# Top.net
KiCad netlist of a schematic drawn in Altium Designer
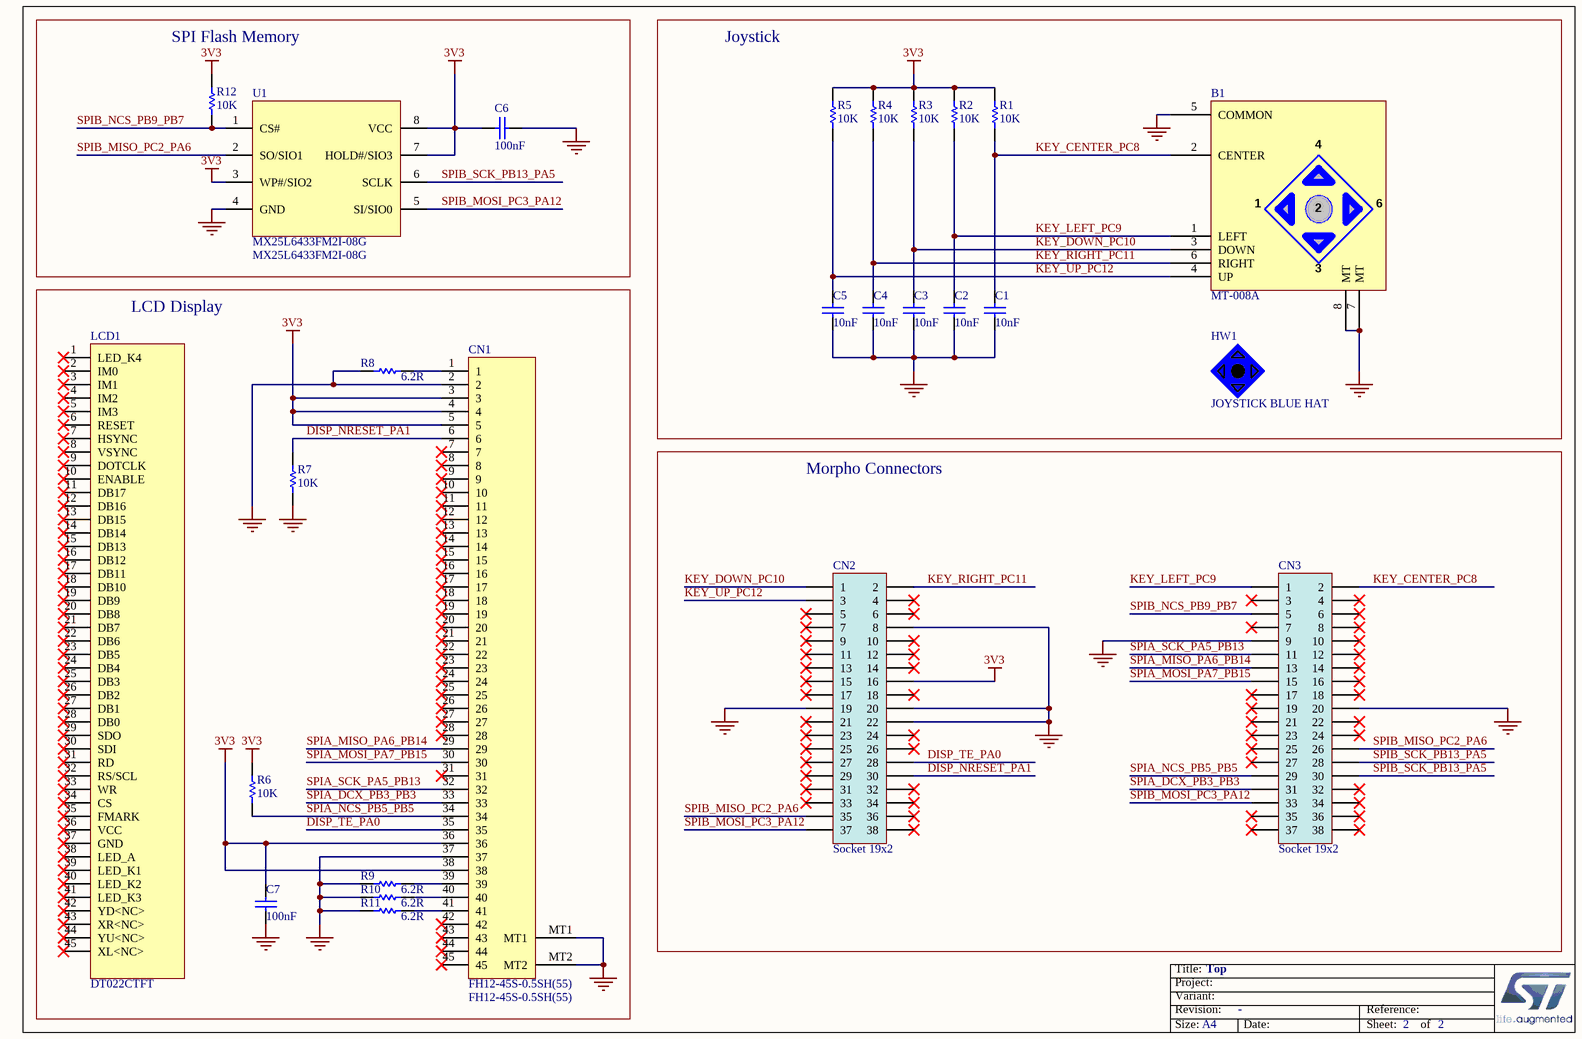
[diagram p0: Top.SchDoc]

(export (version "E")
  (design (tool "Eeschema 10.0.6"))
  (components
    (comp (ref "B1")
      (value "MT-008A")
      (footprint "SWI_XIEJIA_MT-008A_6P")
      (description "Joystick, 4 dir, 1 OK")
      (fields
        (field (name "INTERNAL_PART_NUMBER") "MCD-00132")
        (field (name "MANUFACTURER") "XIEJIA ELECTRONICS")
        (field (name "PROVIDED_BY") "SUBCO")
      )
      (libsource (lib "MCD_PARTS_database") (part "Joystick MT-008A_M"))
    )
    (comp (ref "C1")
      (value "10nF")
      (footprint "C0603")
      (description "Capacitor,10nF,100V,X7R,10%,0603")
      (fields
        (field (name "INTERNAL_PART_NUMBER") "MCD-01098")
        (field (name "MANUFACTURER_PART_NUMBER") "CC0603KRX7R0BB103")
        (field (name "PROVIDED_BY") "SUBCO")
      )
      (libsource (lib "MCD_PARTS_database") (part "Capacitor"))
    )
    (comp (ref "C2")
      (value "10nF")
      (footprint "C0603")
      (description "Capacitor,10nF,100V,X7R,10%,0603")
      (fields
        (field (name "INTERNAL_PART_NUMBER") "MCD-01098")
        (field (name "MANUFACTURER_PART_NUMBER") "CC0603KRX7R0BB103")
        (field (name "PROVIDED_BY") "SUBCO")
      )
      (libsource (lib "MCD_PARTS_database") (part "Capacitor"))
    )
    (comp (ref "C3")
      (value "10nF")
      (footprint "C0603")
      (description "Capacitor,10nF,100V,X7R,10%,0603")
      (fields
        (field (name "INTERNAL_PART_NUMBER") "MCD-01098")
        (field (name "MANUFACTURER_PART_NUMBER") "CC0603KRX7R0BB103")
        (field (name "PROVIDED_BY") "SUBCO")
      )
      (libsource (lib "MCD_PARTS_database") (part "Capacitor"))
    )
    (comp (ref "C4")
      (value "10nF")
      (footprint "C0603")
      (description "Capacitor,10nF,100V,X7R,10%,0603")
      (fields
        (field (name "INTERNAL_PART_NUMBER") "MCD-01098")
        (field (name "MANUFACTURER_PART_NUMBER") "CC0603KRX7R0BB103")
        (field (name "PROVIDED_BY") "SUBCO")
      )
      (libsource (lib "MCD_PARTS_database") (part "Capacitor"))
    )
    (comp (ref "C5")
      (value "10nF")
      (footprint "C0603")
      (description "Capacitor,10nF,100V,X7R,10%,0603")
      (fields
        (field (name "INTERNAL_PART_NUMBER") "MCD-01098")
        (field (name "MANUFACTURER_PART_NUMBER") "CC0603KRX7R0BB103")
        (field (name "PROVIDED_BY") "SUBCO")
      )
      (libsource (lib "MCD_PARTS_database") (part "Capacitor"))
    )
    (comp (ref "C6")
      (value "100nF")
      (footprint "C0603")
      (description "Capacitor, MLCC, 100nF, 6V3, X5R, 10%, 0603, T=0,8mm")
      (fields
        (field (name "INTERNAL_PART_NUMBER") "MCD-00237")
        (field (name "MANUFACTURER_PART_NUMBER") "CC0603KRX5R5BB104")
        (field (name "PROVIDED_BY") "SUBCO")
      )
      (libsource (lib "MCD_PARTS_database") (part "Capacitor"))
    )
    (comp (ref "C7")
      (value "100nF")
      (footprint "C0603")
      (description "Capacitor, MLCC, 100nF, 6V3, X5R, 10%, 0603, T=0,8mm")
      (fields
        (field (name "INTERNAL_PART_NUMBER") "MCD-00237")
        (field (name "MANUFACTURER_PART_NUMBER") "CC0603KRX5R5BB104")
        (field (name "PROVIDED_BY") "SUBCO")
      )
      (libsource (lib "MCD_PARTS_database") (part "Capacitor"))
    )
    (comp (ref "CN1")
      (value "FH12-45S-0.5SH(55)")
      (footprint "CON_HRS_FH12-45S-05SH")
      (description "45 pins P 0.5 surface mount connector")
      (fields
        (field (name "INTERNAL_PART_NUMBER") "MCD-01980")
        (field (name "ALTIUM_VALUE") "FH12-45S-0.5SH(55)")
        (field (name "MANUFACTURER") "HIROSE")
        (field (name "PROVIDED_BY") "SUBCO")
      )
      (libsource (lib "MCD_PARTS_database") (part "FH12-45S-0.5SH(55)"))
    )
    (comp (ref "CN2")
      (value "Socket 19x2")
      (footprint "CON_SAMTEC_SSW-119-01-X-D")
      (description "Socket, 19x2, 2.54mm, VR, TH, Height 8.51mm/2.64mm")
      (fields
        (field (name "INTERNAL_PART_NUMBER") "MCD-01845")
        (field (name "MANUFACTURER_PART_NUMBER") "SSW-119-01-x-D")
        (field (name "PROVIDED_BY") "SUBCO")
      )
      (libsource (lib "MCD_PARTS_database") (part "Socket 19x2"))
    )
    (comp (ref "CN3")
      (value "Socket 19x2")
      (footprint "CON_SAMTEC_SSW-119-01-X-D")
      (description "Socket, 19x2, 2.54mm, VR, TH, Height 8.51mm/2.64mm")
      (fields
        (field (name "INTERNAL_PART_NUMBER") "MCD-01845")
        (field (name "MANUFACTURER_PART_NUMBER") "SSW-119-01-x-D")
        (field (name "PROVIDED_BY") "SUBCO")
      )
      (libsource (lib "MCD_PARTS_database") (part "Socket 19x2"))
    )
    (comp (ref "HW1")
      (value "JOYSTICK BLUE HAT")
      (description "Joystick Blue Hat")
      (fields
        (field (name "INTERNAL_PART_NUMBER") "MCD-01337")
        (field (name "MANUFACTURER_PART_NUMBER") "PB-504")
        (field (name "PROVIDED_BY") "SUBCO")
      )
      (libsource (lib "MCD_PARTS_database") (part "JOYSTICK_BLUE_HAT"))
    )
    (comp (ref "LCD1")
      (value "DT022CTFT")
      (footprint "LCD_DISPLAYTECH_DT022CTFT_45P_P050")
      (description "240x320 2.2inch display")
      (fields
        (field (name "INTERNAL_PART_NUMBER") "MCD-01982")
        (field (name "MANUFACTURER") "DISPLAYTECH")
        (field (name "PROVIDED_BY") "SUBCO")
      )
      (libsource (lib "MCD_PARTS_database") (part "DT022CTFT"))
    )
    (comp (ref "R1")
      (value "10K")
      (footprint "R0603")
      (description "Resistor,10K,0603,1%,1/10W")
      (fields
        (field (name "INTERNAL_PART_NUMBER") "MCD-00220")
        (field (name "MANUFACTURER_PART_NUMBER") "RC0603FR-0710KL")
        (field (name "PROVIDED_BY") "SUBCO")
      )
      (libsource (lib "MCD_PARTS_database") (part "Resistor"))
    )
    (comp (ref "R2")
      (value "10K")
      (footprint "R0603")
      (description "Resistor,10K,0603,1%,1/10W")
      (fields
        (field (name "INTERNAL_PART_NUMBER") "MCD-00220")
        (field (name "MANUFACTURER_PART_NUMBER") "RC0603FR-0710KL")
        (field (name "PROVIDED_BY") "SUBCO")
      )
      (libsource (lib "MCD_PARTS_database") (part "Resistor"))
    )
    (comp (ref "R3")
      (value "10K")
      (footprint "R0603")
      (description "Resistor,10K,0603,1%,1/10W")
      (fields
        (field (name "INTERNAL_PART_NUMBER") "MCD-00220")
        (field (name "MANUFACTURER_PART_NUMBER") "RC0603FR-0710KL")
        (field (name "PROVIDED_BY") "SUBCO")
      )
      (libsource (lib "MCD_PARTS_database") (part "Resistor"))
    )
    (comp (ref "R4")
      (value "10K")
      (footprint "R0603")
      (description "Resistor,10K,0603,1%,1/10W")
      (fields
        (field (name "INTERNAL_PART_NUMBER") "MCD-00220")
        (field (name "MANUFACTURER_PART_NUMBER") "RC0603FR-0710KL")
        (field (name "PROVIDED_BY") "SUBCO")
      )
      (libsource (lib "MCD_PARTS_database") (part "Resistor"))
    )
    (comp (ref "R5")
      (value "10K")
      (footprint "R0603")
      (description "Resistor,10K,0603,1%,1/10W")
      (fields
        (field (name "INTERNAL_PART_NUMBER") "MCD-00220")
        (field (name "MANUFACTURER_PART_NUMBER") "RC0603FR-0710KL")
        (field (name "PROVIDED_BY") "SUBCO")
      )
      (libsource (lib "MCD_PARTS_database") (part "Resistor"))
    )
    (comp (ref "R6")
      (value "10K")
      (footprint "R0603")
      (description "Resistor,10K,0603,1%,1/10W")
      (fields
        (field (name "INTERNAL_PART_NUMBER") "MCD-00220")
        (field (name "MANUFACTURER_PART_NUMBER") "RC0603FR-0710KL")
        (field (name "PROVIDED_BY") "SUBCO")
      )
      (libsource (lib "MCD_PARTS_database") (part "Resistor"))
    )
    (comp (ref "R7")
      (value "10K")
      (footprint "R0603")
      (description "Resistor,10K,0603,1%,1/10W")
      (fields
        (field (name "INTERNAL_PART_NUMBER") "MCD-00220")
        (field (name "MANUFACTURER_PART_NUMBER") "RC0603FR-0710KL")
        (field (name "PROVIDED_BY") "SUBCO")
      )
      (libsource (lib "MCD_PARTS_database") (part "Resistor"))
    )
    (comp (ref "R8")
      (value "6.2R")
      (footprint "R1206_H0P55")
      (description "Resistor,6.2R,1206,1%,0.5W")
      (fields
        (field (name "INTERNAL_PART_NUMBER") "MCD-02101")
        (field (name "MANUFACTURER_PART_NUMBER") "ERJ8BQF6R2V")
        (field (name "PROVIDED_BY") "SUBCO")
      )
      (libsource (lib "MCD_PARTS_database") (part "Resistor"))
    )
    (comp (ref "R9")
      (value "6.2R")
      (footprint "R1206_H0P55")
      (description "Resistor,6.2R,1206,1%,0.5W")
      (fields
        (field (name "INTERNAL_PART_NUMBER") "MCD-02101")
        (field (name "MANUFACTURER_PART_NUMBER") "ERJ8BQF6R2V")
        (field (name "PROVIDED_BY") "SUBCO")
      )
      (libsource (lib "MCD_PARTS_database") (part "Resistor"))
    )
    (comp (ref "R10")
      (value "6.2R")
      (footprint "R1206_H0P55")
      (description "Resistor,6.2R,1206,1%,0.5W")
      (fields
        (field (name "INTERNAL_PART_NUMBER") "MCD-02101")
        (field (name "MANUFACTURER_PART_NUMBER") "ERJ8BQF6R2V")
        (field (name "PROVIDED_BY") "SUBCO")
      )
      (libsource (lib "MCD_PARTS_database") (part "Resistor"))
    )
    (comp (ref "R11")
      (value "6.2R")
      (footprint "R1206_H0P55")
      (description "Resistor,6.2R,1206,1%,0.5W")
      (fields
        (field (name "INTERNAL_PART_NUMBER") "MCD-02101")
        (field (name "MANUFACTURER_PART_NUMBER") "ERJ8BQF6R2V")
        (field (name "PROVIDED_BY") "SUBCO")
      )
      (libsource (lib "MCD_PARTS_database") (part "Resistor"))
    )
    (comp (ref "R12")
      (value "10K")
      (footprint "R0603")
      (description "Resistor,10K,0603,1%,1/10W")
      (fields
        (field (name "INTERNAL_PART_NUMBER") "MCD-00220")
        (field (name "MANUFACTURER_PART_NUMBER") "RC0603FR-0710KL")
        (field (name "PROVIDED_BY") "SUBCO")
      )
      (libsource (lib "MCD_PARTS_database") (part "Resistor"))
    )
    (comp (ref "U1")
      (value "MX25L6433FM2I-08G")
      (footprint "ICC_SOP8_5P23X5P28_P127")
      (fields
        (field (name "INTERNAL_PART_NUMBER") "MCD-01981")
        (field (name "ALTIUM_VALUE") "MX25L6433FM2I-08G")
        (field (name "MANUFACTURER") "MACRONIX")
        (field (name "PROVIDED_BY") "SUBCO")
      )
      (libsource (lib "MCD_PARTS_database") (part "MX25L6433FM2I-08G"))
    )
  )
  (nets
    (net (code "1") (name "/DISP_NRESET_PA1") (class "Default")
      (node (ref "CN1") (pin "6") (pinfunction "6_6") (pintype "passive"))
      (node (ref "CN2") (pin "30") (pinfunction "30_30") (pintype "passive"))
      (node (ref "R7") (pin "2") (pinfunction "2_2") (pintype "passive"))
    )
    (net (code "2") (name "/DISP_TE_PA0") (class "Default")
      (node (ref "CN1") (pin "35") (pinfunction "35_35") (pintype "passive"))
      (node (ref "CN2") (pin "28") (pinfunction "28_28") (pintype "passive"))
    )
    (net (code "3") (name "/KEY_CENTER_PC8") (class "Default")
      (node (ref "B1") (pin "2") (pinfunction "CENTER_2") (pintype "passive"))
      (node (ref "C1") (pin "2") (pinfunction "2_2") (pintype "passive"))
      (node (ref "CN3") (pin "2") (pinfunction "2_2") (pintype "passive"))
      (node (ref "R1") (pin "2") (pinfunction "2_2") (pintype "passive"))
    )
    (net (code "4") (name "/KEY_DOWN_PC10") (class "Default")
      (node (ref "B1") (pin "3") (pinfunction "DOWN_3") (pintype "passive"))
      (node (ref "C3") (pin "2") (pinfunction "2_2") (pintype "passive"))
      (node (ref "CN2") (pin "1") (pinfunction "1_1") (pintype "passive"))
      (node (ref "R3") (pin "1") (pinfunction "1_1") (pintype "passive"))
    )
    (net (code "5") (name "/KEY_LEFT_PC9") (class "Default")
      (node (ref "B1") (pin "1") (pinfunction "LEFT_1") (pintype "passive"))
      (node (ref "C2") (pin "2") (pinfunction "2_2") (pintype "passive"))
      (node (ref "CN3") (pin "1") (pinfunction "1_1") (pintype "passive"))
      (node (ref "R2") (pin "1") (pinfunction "1_1") (pintype "passive"))
    )
    (net (code "6") (name "/KEY_RIGHT_PC11") (class "Default")
      (node (ref "B1") (pin "6") (pinfunction "RIGHT_6") (pintype "passive"))
      (node (ref "C4") (pin "2") (pinfunction "2_2") (pintype "passive"))
      (node (ref "CN2") (pin "2") (pinfunction "2_2") (pintype "passive"))
      (node (ref "R4") (pin "1") (pinfunction "1_1") (pintype "passive"))
    )
    (net (code "7") (name "/KEY_UP_PC12") (class "Default")
      (node (ref "B1") (pin "4") (pinfunction "UP_4") (pintype "passive"))
      (node (ref "C5") (pin "2") (pinfunction "2_2") (pintype "passive"))
      (node (ref "CN2") (pin "3") (pinfunction "3_3") (pintype "passive"))
      (node (ref "R5") (pin "1") (pinfunction "1_1") (pintype "passive"))
    )
    (net (code "8") (name "/SPIA_DCX_PB3_PB3") (class "Default")
      (node (ref "CN1") (pin "33") (pinfunction "33_33") (pintype "passive"))
      (node (ref "CN3") (pin "31") (pinfunction "31_31") (pintype "passive"))
    )
    (net (code "9") (name "/SPIA_MISO_PA6_PB14") (class "Default")
      (node (ref "CN1") (pin "29") (pinfunction "29_29") (pintype "passive"))
      (node (ref "CN3") (pin "13") (pinfunction "13_13") (pintype "passive"))
    )
    (net (code "10") (name "/SPIA_MOSI_PA7_PB15") (class "Default")
      (node (ref "CN1") (pin "30") (pinfunction "30_30") (pintype "passive"))
      (node (ref "CN3") (pin "15") (pinfunction "15_15") (pintype "passive"))
    )
    (net (code "11") (name "/SPIA_NCS_PB5_PB5") (class "Default")
      (node (ref "CN1") (pin "34") (pinfunction "34_34") (pintype "passive"))
      (node (ref "CN3") (pin "29") (pinfunction "29_29") (pintype "passive"))
      (node (ref "R6") (pin "1") (pinfunction "1_1") (pintype "passive"))
    )
    (net (code "12") (name "/SPIA_SCK_PA5_PB13") (class "Default")
      (node (ref "CN1") (pin "32") (pinfunction "32_32") (pintype "passive"))
      (node (ref "CN3") (pin "11") (pinfunction "11_11") (pintype "passive"))
    )
    (net (code "13") (name "/SPIB_MISO_PC2_PA6") (class "Default")
      (node (ref "CN2") (pin "35") (pinfunction "35_35") (pintype "passive"))
      (node (ref "CN3") (pin "26") (pinfunction "26_26") (pintype "passive"))
      (node (ref "U1") (pin "2") (pinfunction "SO/SIO1_2") (pintype "passive"))
    )
    (net (code "14") (name "/SPIB_MOSI_PC3_PA12") (class "Default")
      (node (ref "CN2") (pin "37") (pinfunction "37_37") (pintype "passive"))
      (node (ref "CN3") (pin "33") (pinfunction "33_33") (pintype "passive"))
      (node (ref "U1") (pin "5") (pinfunction "SI/SIO0_5") (pintype "passive"))
    )
    (net (code "15") (name "/SPIB_NCS_PB9_PB7") (class "Default")
      (node (ref "CN3") (pin "5") (pinfunction "5_5") (pintype "passive"))
      (node (ref "R12") (pin "2") (pinfunction "2_2") (pintype "passive"))
      (node (ref "U1") (pin "1") (pinfunction "CS#_1") (pintype "passive"))
    )
    (net (code "16") (name "/SPIB_SCK_PB13_PA5") (class "Default")
      (node (ref "CN3") (pin "28") (pinfunction "28_28") (pintype "passive"))
      (node (ref "CN3") (pin "30") (pinfunction "30_30") (pintype "passive"))
      (node (ref "U1") (pin "6") (pinfunction "SCLK_6") (pintype "passive"))
    )
    (net (code "17") (name "3V3") (class "Default")
      (node (ref "C6") (pin "1") (pinfunction "1_1") (pintype "passive"))
      (node (ref "C7") (pin "2") (pinfunction "2_2") (pintype "passive"))
      (node (ref "CN1") (pin "3") (pinfunction "3_3") (pintype "passive"))
      (node (ref "CN1") (pin "36") (pinfunction "36_36") (pintype "passive"))
      (node (ref "CN1") (pin "38") (pinfunction "38_38") (pintype "passive"))
      (node (ref "CN1") (pin "4") (pinfunction "4_4") (pintype "passive"))
      (node (ref "CN1") (pin "5") (pinfunction "5_5") (pintype "passive"))
      (node (ref "CN2") (pin "16") (pinfunction "16_16") (pintype "passive"))
      (node (ref "R1") (pin "1") (pinfunction "1_1") (pintype "passive"))
      (node (ref "R12") (pin "1") (pinfunction "1_1") (pintype "passive"))
      (node (ref "R2") (pin "2") (pinfunction "2_2") (pintype "passive"))
      (node (ref "R3") (pin "2") (pinfunction "2_2") (pintype "passive"))
      (node (ref "R4") (pin "2") (pinfunction "2_2") (pintype "passive"))
      (node (ref "R5") (pin "2") (pinfunction "2_2") (pintype "passive"))
      (node (ref "R6") (pin "2") (pinfunction "2_2") (pintype "passive"))
      (node (ref "U1") (pin "3") (pinfunction "WP#/SIO2_3") (pintype "passive"))
      (node (ref "U1") (pin "7") (pinfunction "HOLD#/SIO3_7") (pintype "passive"))
      (node (ref "U1") (pin "8") (pinfunction "VCC_8") (pintype "passive"))
    )
    (net (code "18") (name "GND") (class "Default")
      (node (ref "B1") (pin "5") (pinfunction "COMMON_5") (pintype "passive"))
      (node (ref "B1") (pin "7") (pinfunction "MT_7") (pintype "passive"))
      (node (ref "B1") (pin "8") (pinfunction "MT_8") (pintype "passive"))
      (node (ref "C1") (pin "1") (pinfunction "1_1") (pintype "passive"))
      (node (ref "C2") (pin "1") (pinfunction "1_1") (pintype "passive"))
      (node (ref "C3") (pin "1") (pinfunction "1_1") (pintype "passive"))
      (node (ref "C4") (pin "1") (pinfunction "1_1") (pintype "passive"))
      (node (ref "C5") (pin "1") (pinfunction "1_1") (pintype "passive"))
      (node (ref "C6") (pin "2") (pinfunction "2_2") (pintype "passive"))
      (node (ref "C7") (pin "1") (pinfunction "1_1") (pintype "passive"))
      (node (ref "CN1") (pin "2") (pinfunction "2_2") (pintype "passive"))
      (node (ref "CN1") (pin "37") (pinfunction "37_37") (pintype "passive"))
      (node (ref "CN1") (pin "MT1") (pinfunction "MT1_MT1") (pintype "passive"))
      (node (ref "CN1") (pin "MT2") (pinfunction "MT2_MT2") (pintype "passive"))
      (node (ref "CN2") (pin "19") (pinfunction "19_19") (pintype "passive"))
      (node (ref "CN2") (pin "20") (pinfunction "20_20") (pintype "passive"))
      (node (ref "CN2") (pin "22") (pinfunction "22_22") (pintype "passive"))
      (node (ref "CN2") (pin "8") (pinfunction "8_8") (pintype "passive"))
      (node (ref "CN3") (pin "20") (pinfunction "20_20") (pintype "passive"))
      (node (ref "CN3") (pin "9") (pinfunction "9_9") (pintype "passive"))
      (node (ref "R10") (pin "1") (pinfunction "1_1") (pintype "passive"))
      (node (ref "R11") (pin "1") (pinfunction "1_1") (pintype "passive"))
      (node (ref "R7") (pin "1") (pinfunction "1_1") (pintype "passive"))
      (node (ref "R8") (pin "1") (pinfunction "1_1") (pintype "passive"))
      (node (ref "R9") (pin "1") (pinfunction "1_1") (pintype "passive"))
      (node (ref "U1") (pin "4") (pinfunction "GND_4") (pintype "passive"))
    )
    (net (code "19") (name "Net-(CN1-Pad1)") (class "Default")
      (node (ref "CN1") (pin "1") (pinfunction "1_1") (pintype "passive"))
      (node (ref "R8") (pin "2") (pinfunction "2_2") (pintype "passive"))
    )
    (net (code "20") (name "Net-(CN1-Pad39)") (class "Default")
      (node (ref "CN1") (pin "39") (pinfunction "39_39") (pintype "passive"))
      (node (ref "R9") (pin "2") (pinfunction "2_2") (pintype "passive"))
    )
    (net (code "21") (name "Net-(CN1-Pad40)") (class "Default")
      (node (ref "CN1") (pin "40") (pinfunction "40_40") (pintype "passive"))
      (node (ref "R10") (pin "2") (pinfunction "2_2") (pintype "passive"))
    )
    (net (code "22") (name "Net-(CN1-Pad41)") (class "Default")
      (node (ref "CN1") (pin "41") (pinfunction "41_41") (pintype "passive"))
      (node (ref "R11") (pin "2") (pinfunction "2_2") (pintype "passive"))
    )
    (net (code "23") (name "unconnected-(CN1-Pad7)") (class "Default")
      (node (ref "CN1") (pin "7") (pinfunction "7_7") (pintype "passive+no_connect"))
    )
    (net (code "24") (name "unconnected-(CN1-Pad8)") (class "Default")
      (node (ref "CN1") (pin "8") (pinfunction "8_8") (pintype "passive+no_connect"))
    )
    (net (code "25") (name "unconnected-(CN1-Pad9)") (class "Default")
      (node (ref "CN1") (pin "9") (pinfunction "9_9") (pintype "passive+no_connect"))
    )
    (net (code "26") (name "unconnected-(CN1-Pad10)") (class "Default")
      (node (ref "CN1") (pin "10") (pinfunction "10_10") (pintype "passive+no_connect"))
    )
    (net (code "27") (name "unconnected-(CN1-Pad11)") (class "Default")
      (node (ref "CN1") (pin "11") (pinfunction "11_11") (pintype "passive+no_connect"))
    )
    (net (code "28") (name "unconnected-(CN1-Pad12)") (class "Default")
      (node (ref "CN1") (pin "12") (pinfunction "12_12") (pintype "passive+no_connect"))
    )
    (net (code "29") (name "unconnected-(CN1-Pad13)") (class "Default")
      (node (ref "CN1") (pin "13") (pinfunction "13_13") (pintype "passive+no_connect"))
    )
    (net (code "30") (name "unconnected-(CN1-Pad14)") (class "Default")
      (node (ref "CN1") (pin "14") (pinfunction "14_14") (pintype "passive+no_connect"))
    )
    (net (code "31") (name "unconnected-(CN1-Pad15)") (class "Default")
      (node (ref "CN1") (pin "15") (pinfunction "15_15") (pintype "passive+no_connect"))
    )
    (net (code "32") (name "unconnected-(CN1-Pad16)") (class "Default")
      (node (ref "CN1") (pin "16") (pinfunction "16_16") (pintype "passive+no_connect"))
    )
    (net (code "33") (name "unconnected-(CN1-Pad17)") (class "Default")
      (node (ref "CN1") (pin "17") (pinfunction "17_17") (pintype "passive+no_connect"))
    )
    (net (code "34") (name "unconnected-(CN1-Pad18)") (class "Default")
      (node (ref "CN1") (pin "18") (pinfunction "18_18") (pintype "passive+no_connect"))
    )
    (net (code "35") (name "unconnected-(CN1-Pad19)") (class "Default")
      (node (ref "CN1") (pin "19") (pinfunction "19_19") (pintype "passive+no_connect"))
    )
    (net (code "36") (name "unconnected-(CN1-Pad20)") (class "Default")
      (node (ref "CN1") (pin "20") (pinfunction "20_20") (pintype "passive+no_connect"))
    )
    (net (code "37") (name "unconnected-(CN1-Pad21)") (class "Default")
      (node (ref "CN1") (pin "21") (pinfunction "21_21") (pintype "passive+no_connect"))
    )
    (net (code "38") (name "unconnected-(CN1-Pad22)") (class "Default")
      (node (ref "CN1") (pin "22") (pinfunction "22_22") (pintype "passive+no_connect"))
    )
    (net (code "39") (name "unconnected-(CN1-Pad23)") (class "Default")
      (node (ref "CN1") (pin "23") (pinfunction "23_23") (pintype "passive+no_connect"))
    )
    (net (code "40") (name "unconnected-(CN1-Pad24)") (class "Default")
      (node (ref "CN1") (pin "24") (pinfunction "24_24") (pintype "passive+no_connect"))
    )
    (net (code "41") (name "unconnected-(CN1-Pad25)") (class "Default")
      (node (ref "CN1") (pin "25") (pinfunction "25_25") (pintype "passive+no_connect"))
    )
    (net (code "42") (name "unconnected-(CN1-Pad26)") (class "Default")
      (node (ref "CN1") (pin "26") (pinfunction "26_26") (pintype "passive+no_connect"))
    )
    (net (code "43") (name "unconnected-(CN1-Pad27)") (class "Default")
      (node (ref "CN1") (pin "27") (pinfunction "27_27") (pintype "passive+no_connect"))
    )
    (net (code "44") (name "unconnected-(CN1-Pad28)") (class "Default")
      (node (ref "CN1") (pin "28") (pinfunction "28_28") (pintype "passive+no_connect"))
    )
    (net (code "45") (name "unconnected-(CN1-Pad31)") (class "Default")
      (node (ref "CN1") (pin "31") (pinfunction "31_31") (pintype "passive+no_connect"))
    )
    (net (code "46") (name "unconnected-(CN1-Pad42)") (class "Default")
      (node (ref "CN1") (pin "42") (pinfunction "42_42") (pintype "passive+no_connect"))
    )
    (net (code "47") (name "unconnected-(CN1-Pad43)") (class "Default")
      (node (ref "CN1") (pin "43") (pinfunction "43_43") (pintype "passive+no_connect"))
    )
    (net (code "48") (name "unconnected-(CN1-Pad44)") (class "Default")
      (node (ref "CN1") (pin "44") (pinfunction "44_44") (pintype "passive+no_connect"))
    )
    (net (code "49") (name "unconnected-(CN1-Pad45)") (class "Default")
      (node (ref "CN1") (pin "45") (pinfunction "45_45") (pintype "passive+no_connect"))
    )
    (net (code "50") (name "unconnected-(CN2-Pad4)") (class "Default")
      (node (ref "CN2") (pin "4") (pinfunction "4_4") (pintype "passive+no_connect"))
    )
    (net (code "51") (name "unconnected-(CN2-Pad5)") (class "Default")
      (node (ref "CN2") (pin "5") (pinfunction "5_5") (pintype "passive+no_connect"))
    )
    (net (code "52") (name "unconnected-(CN2-Pad6)") (class "Default")
      (node (ref "CN2") (pin "6") (pinfunction "6_6") (pintype "passive+no_connect"))
    )
    (net (code "53") (name "unconnected-(CN2-Pad7)") (class "Default")
      (node (ref "CN2") (pin "7") (pinfunction "7_7") (pintype "passive+no_connect"))
    )
    (net (code "54") (name "unconnected-(CN2-Pad9)") (class "Default")
      (node (ref "CN2") (pin "9") (pinfunction "9_9") (pintype "passive+no_connect"))
    )
    (net (code "55") (name "unconnected-(CN2-Pad10)") (class "Default")
      (node (ref "CN2") (pin "10") (pinfunction "10_10") (pintype "passive+no_connect"))
    )
    (net (code "56") (name "unconnected-(CN2-Pad11)") (class "Default")
      (node (ref "CN2") (pin "11") (pinfunction "11_11") (pintype "passive+no_connect"))
    )
    (net (code "57") (name "unconnected-(CN2-Pad12)") (class "Default")
      (node (ref "CN2") (pin "12") (pinfunction "12_12") (pintype "passive+no_connect"))
    )
    (net (code "58") (name "unconnected-(CN2-Pad13)") (class "Default")
      (node (ref "CN2") (pin "13") (pinfunction "13_13") (pintype "passive+no_connect"))
    )
    (net (code "59") (name "unconnected-(CN2-Pad14)") (class "Default")
      (node (ref "CN2") (pin "14") (pinfunction "14_14") (pintype "passive+no_connect"))
    )
    (net (code "60") (name "unconnected-(CN2-Pad15)") (class "Default")
      (node (ref "CN2") (pin "15") (pinfunction "15_15") (pintype "passive+no_connect"))
    )
    (net (code "61") (name "unconnected-(CN2-Pad17)") (class "Default")
      (node (ref "CN2") (pin "17") (pinfunction "17_17") (pintype "passive+no_connect"))
    )
    (net (code "62") (name "unconnected-(CN2-Pad18)") (class "Default")
      (node (ref "CN2") (pin "18") (pinfunction "18_18") (pintype "passive+no_connect"))
    )
    (net (code "63") (name "unconnected-(CN2-Pad21)") (class "Default")
      (node (ref "CN2") (pin "21") (pinfunction "21_21") (pintype "passive+no_connect"))
    )
    (net (code "64") (name "unconnected-(CN2-Pad23)") (class "Default")
      (node (ref "CN2") (pin "23") (pinfunction "23_23") (pintype "passive+no_connect"))
    )
    (net (code "65") (name "unconnected-(CN2-Pad24)") (class "Default")
      (node (ref "CN2") (pin "24") (pinfunction "24_24") (pintype "passive+no_connect"))
    )
    (net (code "66") (name "unconnected-(CN2-Pad25)") (class "Default")
      (node (ref "CN2") (pin "25") (pinfunction "25_25") (pintype "passive+no_connect"))
    )
    (net (code "67") (name "unconnected-(CN2-Pad26)") (class "Default")
      (node (ref "CN2") (pin "26") (pinfunction "26_26") (pintype "passive+no_connect"))
    )
    (net (code "68") (name "unconnected-(CN2-Pad27)") (class "Default")
      (node (ref "CN2") (pin "27") (pinfunction "27_27") (pintype "passive+no_connect"))
    )
    (net (code "69") (name "unconnected-(CN2-Pad29)") (class "Default")
      (node (ref "CN2") (pin "29") (pinfunction "29_29") (pintype "passive+no_connect"))
    )
    (net (code "70") (name "unconnected-(CN2-Pad31)") (class "Default")
      (node (ref "CN2") (pin "31") (pinfunction "31_31") (pintype "passive+no_connect"))
    )
    (net (code "71") (name "unconnected-(CN2-Pad32)") (class "Default")
      (node (ref "CN2") (pin "32") (pinfunction "32_32") (pintype "passive+no_connect"))
    )
    (net (code "72") (name "unconnected-(CN2-Pad33)") (class "Default")
      (node (ref "CN2") (pin "33") (pinfunction "33_33") (pintype "passive+no_connect"))
    )
    (net (code "73") (name "unconnected-(CN2-Pad34)") (class "Default")
      (node (ref "CN2") (pin "34") (pinfunction "34_34") (pintype "passive+no_connect"))
    )
    (net (code "74") (name "unconnected-(CN2-Pad36)") (class "Default")
      (node (ref "CN2") (pin "36") (pinfunction "36_36") (pintype "passive+no_connect"))
    )
    (net (code "75") (name "unconnected-(CN2-Pad38)") (class "Default")
      (node (ref "CN2") (pin "38") (pinfunction "38_38") (pintype "passive+no_connect"))
    )
    (net (code "76") (name "unconnected-(CN3-Pad3)") (class "Default")
      (node (ref "CN3") (pin "3") (pinfunction "3_3") (pintype "passive+no_connect"))
    )
    (net (code "77") (name "unconnected-(CN3-Pad4)") (class "Default")
      (node (ref "CN3") (pin "4") (pinfunction "4_4") (pintype "passive+no_connect"))
    )
    (net (code "78") (name "unconnected-(CN3-Pad6)") (class "Default")
      (node (ref "CN3") (pin "6") (pinfunction "6_6") (pintype "passive+no_connect"))
    )
    (net (code "79") (name "unconnected-(CN3-Pad7)") (class "Default")
      (node (ref "CN3") (pin "7") (pinfunction "7_7") (pintype "passive+no_connect"))
    )
    (net (code "80") (name "unconnected-(CN3-Pad8)") (class "Default")
      (node (ref "CN3") (pin "8") (pinfunction "8_8") (pintype "passive+no_connect"))
    )
    (net (code "81") (name "unconnected-(CN3-Pad10)") (class "Default")
      (node (ref "CN3") (pin "10") (pinfunction "10_10") (pintype "passive+no_connect"))
    )
    (net (code "82") (name "unconnected-(CN3-Pad12)") (class "Default")
      (node (ref "CN3") (pin "12") (pinfunction "12_12") (pintype "passive+no_connect"))
    )
    (net (code "83") (name "unconnected-(CN3-Pad14)") (class "Default")
      (node (ref "CN3") (pin "14") (pinfunction "14_14") (pintype "passive+no_connect"))
    )
    (net (code "84") (name "unconnected-(CN3-Pad16)") (class "Default")
      (node (ref "CN3") (pin "16") (pinfunction "16_16") (pintype "passive+no_connect"))
    )
    (net (code "85") (name "unconnected-(CN3-Pad17)") (class "Default")
      (node (ref "CN3") (pin "17") (pinfunction "17_17") (pintype "passive+no_connect"))
    )
    (net (code "86") (name "unconnected-(CN3-Pad18)") (class "Default")
      (node (ref "CN3") (pin "18") (pinfunction "18_18") (pintype "passive+no_connect"))
    )
    (net (code "87") (name "unconnected-(CN3-Pad19)") (class "Default")
      (node (ref "CN3") (pin "19") (pinfunction "19_19") (pintype "passive+no_connect"))
    )
    (net (code "88") (name "unconnected-(CN3-Pad21)") (class "Default")
      (node (ref "CN3") (pin "21") (pinfunction "21_21") (pintype "passive+no_connect"))
    )
    (net (code "89") (name "unconnected-(CN3-Pad22)") (class "Default")
      (node (ref "CN3") (pin "22") (pinfunction "22_22") (pintype "passive+no_connect"))
    )
    (net (code "90") (name "unconnected-(CN3-Pad23)") (class "Default")
      (node (ref "CN3") (pin "23") (pinfunction "23_23") (pintype "passive+no_connect"))
    )
    (net (code "91") (name "unconnected-(CN3-Pad24)") (class "Default")
      (node (ref "CN3") (pin "24") (pinfunction "24_24") (pintype "passive+no_connect"))
    )
    (net (code "92") (name "unconnected-(CN3-Pad25)") (class "Default")
      (node (ref "CN3") (pin "25") (pinfunction "25_25") (pintype "passive+no_connect"))
    )
    (net (code "93") (name "unconnected-(CN3-Pad27)") (class "Default")
      (node (ref "CN3") (pin "27") (pinfunction "27_27") (pintype "passive+no_connect"))
    )
    (net (code "94") (name "unconnected-(CN3-Pad32)") (class "Default")
      (node (ref "CN3") (pin "32") (pinfunction "32_32") (pintype "passive+no_connect"))
    )
    (net (code "95") (name "unconnected-(CN3-Pad34)") (class "Default")
      (node (ref "CN3") (pin "34") (pinfunction "34_34") (pintype "passive+no_connect"))
    )
    (net (code "96") (name "unconnected-(CN3-Pad35)") (class "Default")
      (node (ref "CN3") (pin "35") (pinfunction "35_35") (pintype "passive+no_connect"))
    )
    (net (code "97") (name "unconnected-(CN3-Pad36)") (class "Default")
      (node (ref "CN3") (pin "36") (pinfunction "36_36") (pintype "passive+no_connect"))
    )
    (net (code "98") (name "unconnected-(CN3-Pad37)") (class "Default")
      (node (ref "CN3") (pin "37") (pinfunction "37_37") (pintype "passive+no_connect"))
    )
    (net (code "99") (name "unconnected-(CN3-Pad38)") (class "Default")
      (node (ref "CN3") (pin "38") (pinfunction "38_38") (pintype "passive+no_connect"))
    )
    (net (code "100") (name "unconnected-(LCD1-CS-Pad34)") (class "Default")
      (node (ref "LCD1") (pin "34") (pinfunction "CS_34") (pintype "passive+no_connect"))
    )
    (net (code "101") (name "unconnected-(LCD1-DB0-Pad28)") (class "Default")
      (node (ref "LCD1") (pin "28") (pinfunction "DB0_28") (pintype "passive+no_connect"))
    )
    (net (code "102") (name "unconnected-(LCD1-DB1-Pad27)") (class "Default")
      (node (ref "LCD1") (pin "27") (pinfunction "DB1_27") (pintype "passive+no_connect"))
    )
    (net (code "103") (name "unconnected-(LCD1-DB2-Pad26)") (class "Default")
      (node (ref "LCD1") (pin "26") (pinfunction "DB2_26") (pintype "passive+no_connect"))
    )
    (net (code "104") (name "unconnected-(LCD1-DB3-Pad25)") (class "Default")
      (node (ref "LCD1") (pin "25") (pinfunction "DB3_25") (pintype "passive+no_connect"))
    )
    (net (code "105") (name "unconnected-(LCD1-DB4-Pad24)") (class "Default")
      (node (ref "LCD1") (pin "24") (pinfunction "DB4_24") (pintype "passive+no_connect"))
    )
    (net (code "106") (name "unconnected-(LCD1-DB5-Pad23)") (class "Default")
      (node (ref "LCD1") (pin "23") (pinfunction "DB5_23") (pintype "passive+no_connect"))
    )
    (net (code "107") (name "unconnected-(LCD1-DB6-Pad22)") (class "Default")
      (node (ref "LCD1") (pin "22") (pinfunction "DB6_22") (pintype "passive+no_connect"))
    )
    (net (code "108") (name "unconnected-(LCD1-DB7-Pad21)") (class "Default")
      (node (ref "LCD1") (pin "21") (pinfunction "DB7_21") (pintype "passive+no_connect"))
    )
    (net (code "109") (name "unconnected-(LCD1-DB8-Pad20)") (class "Default")
      (node (ref "LCD1") (pin "20") (pinfunction "DB8_20") (pintype "passive+no_connect"))
    )
    (net (code "110") (name "unconnected-(LCD1-DB9-Pad19)") (class "Default")
      (node (ref "LCD1") (pin "19") (pinfunction "DB9_19") (pintype "passive+no_connect"))
    )
    (net (code "111") (name "unconnected-(LCD1-DB10-Pad18)") (class "Default")
      (node (ref "LCD1") (pin "18") (pinfunction "DB10_18") (pintype "passive+no_connect"))
    )
    (net (code "112") (name "unconnected-(LCD1-DB11-Pad17)") (class "Default")
      (node (ref "LCD1") (pin "17") (pinfunction "DB11_17") (pintype "passive+no_connect"))
    )
    (net (code "113") (name "unconnected-(LCD1-DB12-Pad16)") (class "Default")
      (node (ref "LCD1") (pin "16") (pinfunction "DB12_16") (pintype "passive+no_connect"))
    )
    (net (code "114") (name "unconnected-(LCD1-DB13-Pad15)") (class "Default")
      (node (ref "LCD1") (pin "15") (pinfunction "DB13_15") (pintype "passive+no_connect"))
    )
    (net (code "115") (name "unconnected-(LCD1-DB14-Pad14)") (class "Default")
      (node (ref "LCD1") (pin "14") (pinfunction "DB14_14") (pintype "passive+no_connect"))
    )
    (net (code "116") (name "unconnected-(LCD1-DB15-Pad13)") (class "Default")
      (node (ref "LCD1") (pin "13") (pinfunction "DB15_13") (pintype "passive+no_connect"))
    )
    (net (code "117") (name "unconnected-(LCD1-DB16-Pad12)") (class "Default")
      (node (ref "LCD1") (pin "12") (pinfunction "DB16_12") (pintype "passive+no_connect"))
    )
    (net (code "118") (name "unconnected-(LCD1-DB17-Pad11)") (class "Default")
      (node (ref "LCD1") (pin "11") (pinfunction "DB17_11") (pintype "passive+no_connect"))
    )
    (net (code "119") (name "unconnected-(LCD1-DOTCLK-Pad9)") (class "Default")
      (node (ref "LCD1") (pin "9") (pinfunction "DOTCLK_9") (pintype "passive+no_connect"))
    )
    (net (code "120") (name "unconnected-(LCD1-ENABLE-Pad10)") (class "Default")
      (node (ref "LCD1") (pin "10") (pinfunction "ENABLE_10") (pintype "passive+no_connect"))
    )
    (net (code "121") (name "unconnected-(LCD1-FMARK-Pad35)") (class "Default")
      (node (ref "LCD1") (pin "35") (pinfunction "FMARK_35") (pintype "passive+no_connect"))
    )
    (net (code "122") (name "unconnected-(LCD1-GND-Pad37)") (class "Default")
      (node (ref "LCD1") (pin "37") (pinfunction "GND_37") (pintype "passive+no_connect"))
    )
    (net (code "123") (name "unconnected-(LCD1-HSYNC-Pad7)") (class "Default")
      (node (ref "LCD1") (pin "7") (pinfunction "HSYNC_7") (pintype "passive+no_connect"))
    )
    (net (code "124") (name "unconnected-(LCD1-IM0-Pad2)") (class "Default")
      (node (ref "LCD1") (pin "2") (pinfunction "IM0_2") (pintype "passive+no_connect"))
    )
    (net (code "125") (name "unconnected-(LCD1-IM1-Pad3)") (class "Default")
      (node (ref "LCD1") (pin "3") (pinfunction "IM1_3") (pintype "passive+no_connect"))
    )
    (net (code "126") (name "unconnected-(LCD1-IM2-Pad4)") (class "Default")
      (node (ref "LCD1") (pin "4") (pinfunction "IM2_4") (pintype "passive+no_connect"))
    )
    (net (code "127") (name "unconnected-(LCD1-IM3-Pad5)") (class "Default")
      (node (ref "LCD1") (pin "5") (pinfunction "IM3_5") (pintype "passive+no_connect"))
    )
    (net (code "128") (name "unconnected-(LCD1-LED_A-Pad38)") (class "Default")
      (node (ref "LCD1") (pin "38") (pinfunction "LED_A_38") (pintype "passive+no_connect"))
    )
    (net (code "129") (name "unconnected-(LCD1-LED_K1-Pad39)") (class "Default")
      (node (ref "LCD1") (pin "39") (pinfunction "LED_K1_39") (pintype "passive+no_connect"))
    )
    (net (code "130") (name "unconnected-(LCD1-LED_K2-Pad40)") (class "Default")
      (node (ref "LCD1") (pin "40") (pinfunction "LED_K2_40") (pintype "passive+no_connect"))
    )
    (net (code "131") (name "unconnected-(LCD1-LED_K3-Pad41)") (class "Default")
      (node (ref "LCD1") (pin "41") (pinfunction "LED_K3_41") (pintype "passive+no_connect"))
    )
    (net (code "132") (name "unconnected-(LCD1-LED_K4-Pad1)") (class "Default")
      (node (ref "LCD1") (pin "1") (pinfunction "LED_K4_1") (pintype "passive+no_connect"))
    )
    (net (code "133") (name "unconnected-(LCD1-RD-Pad31)") (class "Default")
      (node (ref "LCD1") (pin "31") (pinfunction "RD_31") (pintype "passive+no_connect"))
    )
    (net (code "134") (name "unconnected-(LCD1-RESET-Pad6)") (class "Default")
      (node (ref "LCD1") (pin "6") (pinfunction "RESET_6") (pintype "passive+no_connect"))
    )
    (net (code "135") (name "unconnected-(LCD1-RS{slash}SCL-Pad32)") (class "Default")
      (node (ref "LCD1") (pin "32") (pinfunction "RS/SCL_32") (pintype "passive+no_connect"))
    )
    (net (code "136") (name "unconnected-(LCD1-SDI-Pad30)") (class "Default")
      (node (ref "LCD1") (pin "30") (pinfunction "SDI_30") (pintype "passive+no_connect"))
    )
    (net (code "137") (name "unconnected-(LCD1-SDO-Pad29)") (class "Default")
      (node (ref "LCD1") (pin "29") (pinfunction "SDO_29") (pintype "passive+no_connect"))
    )
    (net (code "138") (name "unconnected-(LCD1-VCC-Pad36)") (class "Default")
      (node (ref "LCD1") (pin "36") (pinfunction "VCC_36") (pintype "passive+no_connect"))
    )
    (net (code "139") (name "unconnected-(LCD1-VSYNC-Pad8)") (class "Default")
      (node (ref "LCD1") (pin "8") (pinfunction "VSYNC_8") (pintype "passive+no_connect"))
    )
    (net (code "140") (name "unconnected-(LCD1-WR-Pad33)") (class "Default")
      (node (ref "LCD1") (pin "33") (pinfunction "WR_33") (pintype "passive+no_connect"))
    )
    (net (code "141") (name "unconnected-(LCD1-XL<NC>-Pad45)") (class "Default")
      (node (ref "LCD1") (pin "45") (pinfunction "XL<NC>_45") (pintype "passive+no_connect"))
    )
    (net (code "142") (name "unconnected-(LCD1-XR<NC>-Pad43)") (class "Default")
      (node (ref "LCD1") (pin "43") (pinfunction "XR<NC>_43") (pintype "passive+no_connect"))
    )
    (net (code "143") (name "unconnected-(LCD1-YD<NC>-Pad42)") (class "Default")
      (node (ref "LCD1") (pin "42") (pinfunction "YD<NC>_42") (pintype "passive+no_connect"))
    )
    (net (code "144") (name "unconnected-(LCD1-YU<NC>-Pad44)") (class "Default")
      (node (ref "LCD1") (pin "44") (pinfunction "YU<NC>_44") (pintype "passive+no_connect"))
    )
  )
)
